# OBD.net
KiCad netlist of a schematic drawn in Altium Designer
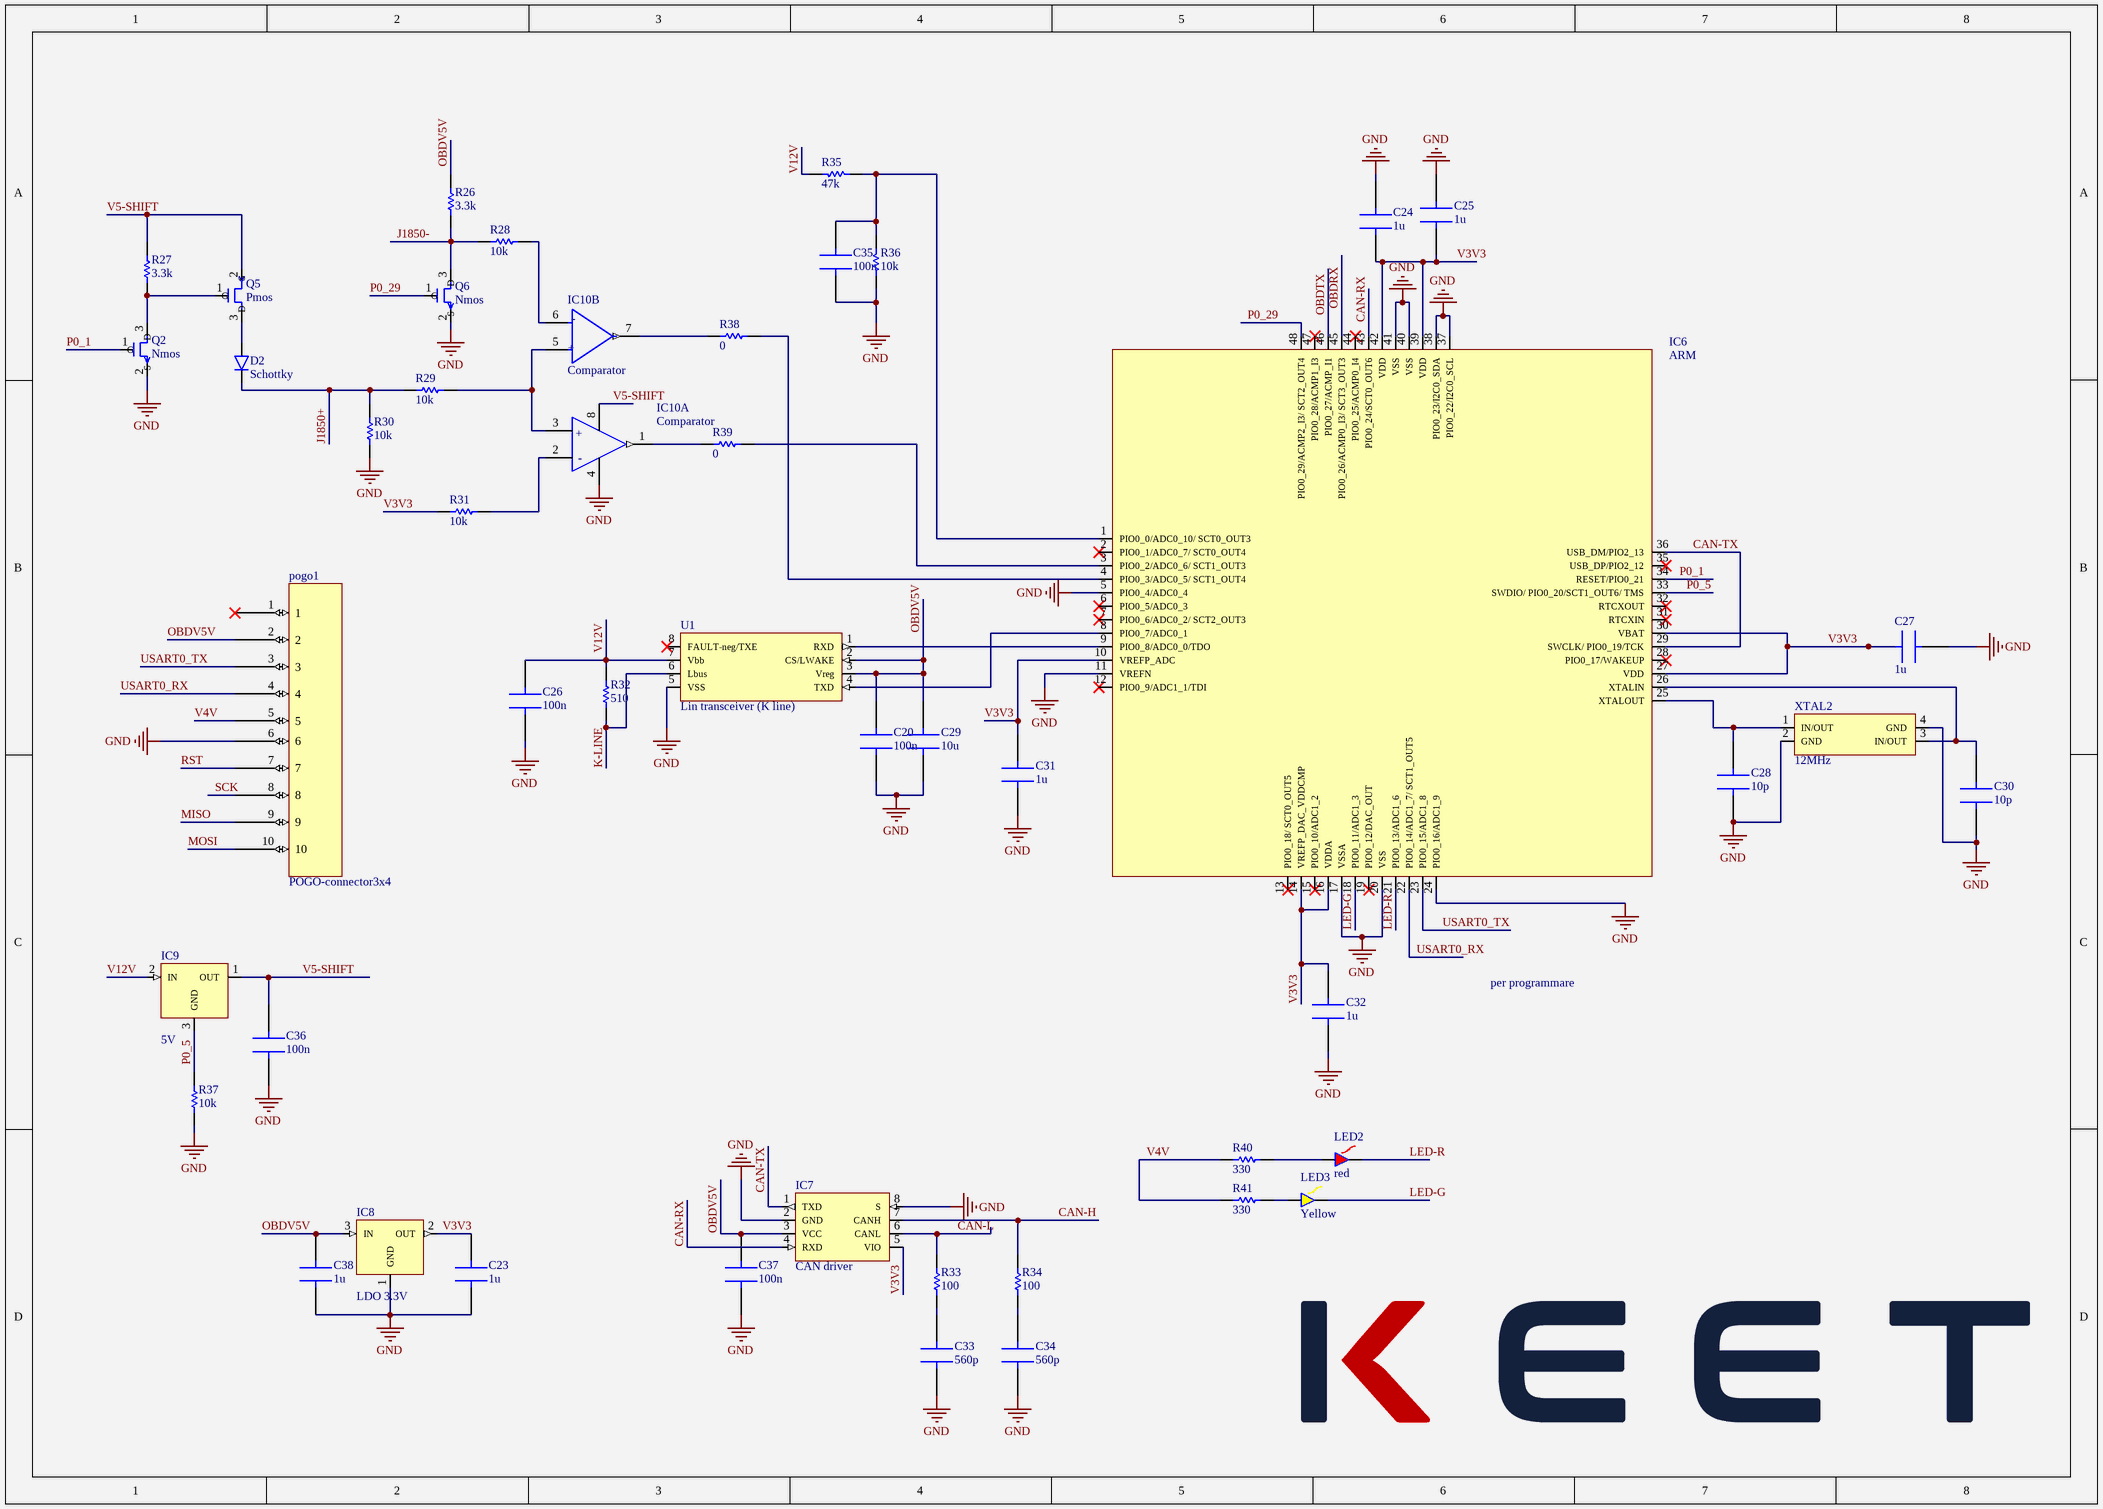
[diagram p0: OBD.SchDoc]

(export (version "E")
  (design (tool "Eeschema 10.0.6"))
  (components
    (comp (ref "C20")
      (value "100n")
      (footprint "CAPC1005X06N")
      (description "CAP CER 0.1UF 50V X5R 0402")
      (fields
        (field (name "MANUFACTURER") "TDK")
        (field (name "MANUFACTURER PART NUMBER") "C1005X5R1H104K050BB")
      )
      (libsource (lib "KeetV2") (part "C1005X5R1H104K050BB"))
    )
    (comp (ref "C23")
      (value "1u")
      (footprint "CAPC1005X06N")
      (description "TAIYO YUDEN - EMK105BJ105KVHF - CAPACITOR,CERAMIC,0402,16V,X5R,1 F, 10% ROHS COMPLIANT: YES")
      (fields
        (field (name "MANUFACTURER") "Taiyo Yuden")
        (field (name "MANUFACTURER PART NUMBER") "EMK105BJ105KVHF")
      )
      (libsource (lib "KeetV2") (part "EMK105BJ105KVHF"))
    )
    (comp (ref "C24")
      (value "1u")
      (footprint "CAPC1005X06N")
      (description "TAIYO YUDEN - EMK105BJ105KVHF - CAPACITOR,CERAMIC,0402,16V,X5R,1 F, 10% ROHS COMPLIANT: YES")
      (fields
        (field (name "MANUFACTURER") "Taiyo Yuden")
        (field (name "MANUFACTURER PART NUMBER") "EMK105BJ105KVHF")
      )
      (libsource (lib "KeetV2") (part "EMK105BJ105KVHF"))
    )
    (comp (ref "C25")
      (value "1u")
      (footprint "CAPC1005X06N")
      (description "TAIYO YUDEN - EMK105BJ105KVHF - CAPACITOR,CERAMIC,0402,16V,X5R,1 F, 10% ROHS COMPLIANT: YES")
      (fields
        (field (name "MANUFACTURER") "Taiyo Yuden")
        (field (name "MANUFACTURER PART NUMBER") "EMK105BJ105KVHF")
      )
      (libsource (lib "KeetV2") (part "EMK105BJ105KVHF"))
    )
    (comp (ref "C26")
      (value "100n")
      (footprint "CAPC1005X06N")
      (description "CAP CER 0.1UF 50V X5R 0402")
      (fields
        (field (name "MANUFACTURER") "TDK")
        (field (name "MANUFACTURER PART NUMBER") "C1005X5R1H104K050BB")
      )
      (libsource (lib "KeetV2") (part "C1005X5R1H104K050BB"))
    )
    (comp (ref "C27")
      (value "1u")
      (footprint "CAPC1005X06N")
      (description "TAIYO YUDEN - EMK105BJ105KVHF - CAPACITOR,CERAMIC,0402,16V,X5R,1 F, 10% ROHS COMPLIANT: YES")
      (fields
        (field (name "MANUFACTURER") "Taiyo Yuden")
        (field (name "MANUFACTURER PART NUMBER") "EMK105BJ105KVHF")
      )
      (libsource (lib "KeetV2") (part "EMK105BJ105KVHF"))
    )
    (comp (ref "C28")
      (value "10p")
      (footprint "CAPC1005X06N")
      (fields
        (field (name "MANUFACTURER") "Kyocera AVX")
        (field (name "MANUFACTURER PART NUMBER") "04025A100JAT2A")
        (field (name "TOLERANCE") "5%")
      )
      (libsource (lib "KeetV2") (part "04025A100JAT2A"))
    )
    (comp (ref "C29")
      (value "10u")
      (footprint "CAPC1005X06N")
      (description "Multi-Layer Ceramic Capacitor 10uF X5R 20% 0402 Paper T/R")
      (fields
        (field (name "MANUFACTURER") "Murata")
        (field (name "MANUFACTURER PART NUMBER") "GRM155R60J106ME05J")
      )
      (libsource (lib "KeetV2") (part "GRM155R60J106ME05J"))
    )
    (comp (ref "C30")
      (value "10p")
      (footprint "CAPC1005X06N")
      (fields
        (field (name "MANUFACTURER") "Kyocera AVX")
        (field (name "MANUFACTURER PART NUMBER") "04025A100JAT2A")
        (field (name "TOLERANCE") "5%")
      )
      (libsource (lib "KeetV2") (part "04025A100JAT2A"))
    )
    (comp (ref "C31")
      (value "1u")
      (footprint "CAPC1005X06N")
      (description "TAIYO YUDEN - EMK105BJ105KVHF - CAPACITOR,CERAMIC,0402,16V,X5R,1 F, 10% ROHS COMPLIANT: YES")
      (fields
        (field (name "MANUFACTURER") "Taiyo Yuden")
        (field (name "MANUFACTURER PART NUMBER") "EMK105BJ105KVHF")
      )
      (libsource (lib "KeetV2") (part "EMK105BJ105KVHF"))
    )
    (comp (ref "C32")
      (value "1u")
      (footprint "CAPC1005X06N")
      (description "TAIYO YUDEN - EMK105BJ105KVHF - CAPACITOR,CERAMIC,0402,16V,X5R,1 F, 10% ROHS COMPLIANT: YES")
      (fields
        (field (name "MANUFACTURER") "Taiyo Yuden")
        (field (name "MANUFACTURER PART NUMBER") "EMK105BJ105KVHF")
      )
      (libsource (lib "KeetV2") (part "EMK105BJ105KVHF"))
    )
    (comp (ref "C33")
      (value "560p")
      (footprint "CAPC1005X06N")
      (description "CAP CER 560PF 50V X7R 0402")
      (fields
        (field (name "MANUFACTURER") "Yageo")
        (field (name "MANUFACTURER PART NUMBER") "CC0402KRX7R9BB561")
      )
      (libsource (lib "KeetV2") (part "CC0402KRX7R9BB561"))
    )
    (comp (ref "C34")
      (value "560p")
      (footprint "CAPC1005X06N")
      (description "CAP CER 560PF 50V X7R 0402")
      (fields
        (field (name "MANUFACTURER") "Yageo")
        (field (name "MANUFACTURER PART NUMBER") "CC0402KRX7R9BB561")
      )
      (libsource (lib "KeetV2") (part "CC0402KRX7R9BB561"))
    )
    (comp (ref "C35")
      (value "100n")
      (footprint "CAPC1005X06N")
      (description "CAP CER 0.1UF 16V X7R 0402")
      (fields
        (field (name "MANUFACTURER") "Murata")
        (field (name "MANUFACTURER PART NUMBER") "GRM155R71C104KA88D")
      )
      (libsource (lib "KeetV2") (part "GRM155R71C104KA88D"))
    )
    (comp (ref "C36")
      (value "100n")
      (footprint "CAPC1005X06N")
      (description "CAP CER 0.1UF 16V X7R 0402")
      (fields
        (field (name "MANUFACTURER") "Murata")
        (field (name "MANUFACTURER PART NUMBER") "GRM155R71C104KA88D")
      )
      (libsource (lib "KeetV2") (part "GRM155R71C104KA88D"))
    )
    (comp (ref "C37")
      (value "100n")
      (footprint "CAPC1005X06N")
      (description "CAP CER 0.1UF 50V X5R 0402")
      (fields
        (field (name "MANUFACTURER") "TDK")
        (field (name "MANUFACTURER PART NUMBER") "C1005X5R1H104K050BB")
      )
      (libsource (lib "KeetV2") (part "C1005X5R1H104K050BB"))
    )
    (comp (ref "C38")
      (value "1u")
      (footprint "CAPC1005X06N")
      (description "TAIYO YUDEN - EMK105BJ105KVHF - CAPACITOR,CERAMIC,0402,16V,X5R,1 F, 10% ROHS COMPLIANT: YES")
      (fields
        (field (name "MANUFACTURER") "Taiyo Yuden")
        (field (name "MANUFACTURER PART NUMBER") "EMK105BJ105KVHF")
      )
      (libsource (lib "KeetV2") (part "EMK105BJ105KVHF"))
    )
    (comp (ref "D2")
      (value "Schottky")
      (footprint "TSSOP0P370X135-2N")
      (description "Diode Schottky 100V 0.15A 2Pin SOD123")
      (fields (field (name "MANUFACTURER") "Diodes") (field (name "MANUFACTURER PART NUMBER") "BAT46W-7-F"))
      (libsource (lib "KeetV2") (part "BAT46W-7-F"))
    )
    (comp (ref "IC6")
      (value "ARM")
      (footprint "TSQFP50P898X898X160-48N")
      (description "IC MCU 32BIT 64KB FLASH 48LQFP")
      (fields
        (field (name "MANUFACTURER") "NXP Semiconductors")
        (field (name "MANUFACTURER PART NUMBER") "LPC1517JBD48E")
      )
      (libsource (lib "KeetV2") (part "LPC1517JBD48E"))
    )
    (comp (ref "IC7")
      (value "CAN driver")
      (footprint "SOP127P600X175-8N")
      (description "IC CAN TRANSEIVER HS 8SOIC")
      (fields
        (field (name "MANUFACTURER") "NXP Semiconductors")
        (field (name "MANUFACTURER PART NUMBER") "TJF1051T/3,118")
      )
      (libsource (lib "KeetV2") (part "TJF1051T/3,118"))
    )
    (comp (ref "IC8")
      (value "LDO 3.3V")
      (footprint "SOT95P240X135-3N")
      (description "IC REG LIN 3.3V 150MA SOT23R-3")
      (fields
        (field (name "MANUFACTURER") "Diodes")
        (field (name "MANUFACTURER PART NUMBER") "AP7313-33SRG-7")
      )
      (libsource (lib "KeetV2") (part "AP7313-33SRG-7"))
    )
    (comp (ref "IC9")
      (value "5V")
      (footprint "SOT95P237X111-3N-ver2")
      (description "IC REG LINEAR 5V 100MA SOT23-3")
      (fields
        (field (name "MANUFACTURER") "Texas Instruments")
        (field (name "MANUFACTURER PART NUMBER") "TLV76050DBZT")
      )
      (libsource (lib "KeetV2") (part "TLV76050DBZT"))
    )
    (comp (ref "IC10")
      (value "Comparator")
      (footprint "SOIC127P600X175-8N")
      (description "TEXAS INSTRUMENTS - LM393D - COMPARATOR DUAL, SMD, SOIC8, 393")
      (fields
        (field (name "MANUFACTURER") "Texas Instruments")
        (field (name "MANUFACTURER PART NUMBER") "LM393D")
      )
      (libsource (lib "KeetV2") (part "LM393D"))
    )
    (comp (ref "LED2")
      (value "red")
      (footprint "CAC-0P80X160-2N_ver2")
      (description "AVAGO TECHNOLOGIES - HSMS-C190 - LED, RED, 10MCD, 626NM")
      (fields
        (field (name "MANUFACTURER") "Broadcom Avago")
        (field (name "MANUFACTURER PART NUMBER") "HSMS-C190")
      )
      (libsource (lib "KeetV2") (part "HSMS-C190"))
    )
    (comp (ref "LED3")
      (value "Yellow")
      (footprint "CAC-0P80X160-2N_ver2")
      (fields
        (field (name "MANUFACTURER") "Broadcom Avago")
        (field (name "MANUFACTURER PART NUMBER") "HSMY-C190")
      )
      (libsource (lib "KeetV2") (part "HSMY-C190"))
    )
    (comp (ref "pogo1")
      (value "POGO-connector3x4")
      (footprint "POGO_connector_3x4")
      (description "pad layout for external pogo connector")
      (libsource (lib "KeetV2") (part "POGO-connector3x4"))
    )
    (comp (ref "Q2")
      (value "Nmos")
      (footprint "SOT95P240X135-3N")
      (description "Trans MOSFET N-CH 50V 0.22A 3-Pin SOT-23 T/R")
      (fields
        (field (name "MANUFACTURER") "ON Semiconductor / Fairchild")
        (field (name "MANUFACTURER PART NUMBER") "BSS138")
      )
      (libsource (lib "KeetV2") (part "BSS138"))
    )
    (comp (ref "Q5")
      (value "Pmos")
      (footprint "SOT95P237X111-3N")
      (description "On a Reel of 3000, P-Channel MOSFET, 130 mA, 50 V, 3-Pin SOT-23 ON Semiconductor BSS84LT1G")
      (fields
        (field (name "MANUFACTURER") "ON Semiconductor")
        (field (name "MANUFACTURER PART NUMBER") "BSS84LT1G")
      )
      (libsource (lib "KeetV2") (part "BSS84LT1G"))
    )
    (comp (ref "Q6")
      (value "Nmos")
      (footprint "SOT95P240X135-3N")
      (description "Trans MOSFET N-CH 50V 0.22A 3-Pin SOT-23 T/R")
      (fields
        (field (name "MANUFACTURER") "ON Semiconductor / Fairchild")
        (field (name "MANUFACTURER PART NUMBER") "BSS138")
      )
      (libsource (lib "KeetV2") (part "BSS138"))
    )
    (comp (ref "R26")
      (value "3.3k")
      (footprint "RESC1005X04N")
      (description "PANASONIC - ERJ2RKF3301X - RES, 3K3, 1%, 0.1W, 0402, THICK FILM")
      (fields
        (field (name "MANUFACTURER") "Panasonic")
        (field (name "MANUFACTURER PART NUMBER") "ERJ-2RKF3301X")
      )
      (libsource (lib "KeetV2") (part "ERJ-2RKF3301X"))
    )
    (comp (ref "R27")
      (value "3.3k")
      (footprint "RESC1005X04N")
      (description "PANASONIC - ERJ2RKF3301X - RES, 3K3, 1%, 0.1W, 0402, THICK FILM")
      (fields
        (field (name "MANUFACTURER") "Panasonic")
        (field (name "MANUFACTURER PART NUMBER") "ERJ-2RKF3301X")
      )
      (libsource (lib "KeetV2") (part "ERJ-2RKF3301X"))
    )
    (comp (ref "R28")
      (value "10k")
      (footprint "RESC1005X04N")
      (fields
        (field (name "MANUFACTURER") "Panasonic")
        (field (name "MANUFACTURER PART NUMBER") "ERJ-U02F1002X")
        (field (name "TOLERANCE") "1%")
      )
      (libsource (lib "KeetV2") (part "ERJ-U02F1002X"))
    )
    (comp (ref "R29")
      (value "10k")
      (footprint "RESC1005X04N")
      (fields
        (field (name "MANUFACTURER") "Panasonic")
        (field (name "MANUFACTURER PART NUMBER") "ERJ-U02F1002X")
        (field (name "TOLERANCE") "1%")
      )
      (libsource (lib "KeetV2") (part "ERJ-U02F1002X"))
    )
    (comp (ref "R30")
      (value "10k")
      (footprint "RESC1005X04N")
      (fields
        (field (name "MANUFACTURER") "Panasonic")
        (field (name "MANUFACTURER PART NUMBER") "ERJ-U02F1002X")
        (field (name "TOLERANCE") "1%")
      )
      (libsource (lib "KeetV2") (part "ERJ-U02F1002X"))
    )
    (comp (ref "R31")
      (value "10k")
      (footprint "RESC1005X04N")
      (fields
        (field (name "MANUFACTURER") "Panasonic")
        (field (name "MANUFACTURER PART NUMBER") "ERJ-U02F1002X")
        (field (name "TOLERANCE") "1%")
      )
      (libsource (lib "KeetV2") (part "ERJ-U02F1002X"))
    )
    (comp (ref "R32")
      (value "510")
      (footprint "RESC1005X04N")
      (description "Res Thick Film 0402 510 Ohm 1% 0.063W(1/16W) ±100ppm/C Pad SMD T/R")
      (fields
        (field (name "MANUFACTURER") "Vishay")
        (field (name "MANUFACTURER PART NUMBER") "CRCW0402510RFKEDC")
      )
      (libsource (lib "KeetV2") (part "CRCW0402510RFKEDC"))
    )
    (comp (ref "R33")
      (value "100")
      (footprint "RESC1005X04N")
      (description "RES SMD 100 OHM 0.5% 1/16W 0402")
      (fields
        (field (name "MANUFACTURER") "Panasonic")
        (field (name "MANUFACTURER PART NUMBER") "ERJ-2RHD1000X")
      )
      (libsource (lib "KeetV2") (part "ERJ-2RHD1000X"))
    )
    (comp (ref "R34")
      (value "100")
      (footprint "RESC1005X04N")
      (description "RES SMD 100 OHM 0.5% 1/16W 0402")
      (fields
        (field (name "MANUFACTURER") "Panasonic")
        (field (name "MANUFACTURER PART NUMBER") "ERJ-2RHD1000X")
      )
      (libsource (lib "KeetV2") (part "ERJ-2RHD1000X"))
    )
    (comp (ref "R35")
      (value "47k")
      (footprint "RESC1005X04N")
      (description "Resistor;  Thick Film;  47 Kilohms;  0.063 W;  1%;  SMT;  0402;  TCR 37 ppm/DegC")
      (fields
        (field (name "MANUFACTURER") "Vishay")
        (field (name "MANUFACTURER PART NUMBER") "CRCW040247K0FKED")
      )
      (libsource (lib "KeetV2") (part "CRCW040247K0FKED"))
    )
    (comp (ref "R36")
      (value "10k")
      (footprint "RESC1005X04N")
      (fields
        (field (name "MANUFACTURER") "Panasonic")
        (field (name "MANUFACTURER PART NUMBER") "ERJ-U02F1002X")
        (field (name "TOLERANCE") "1%")
      )
      (libsource (lib "KeetV2") (part "ERJ-U02F1002X"))
    )
    (comp (ref "R37")
      (value "10k")
      (footprint "RESC1005X04N")
      (description "Res Thick Film 0402 10K Ohm 1% 1/16W ±100ppm/°C Molded SMD Paper T/R")
      (fields
        (field (name "MANUFACTURER") "Vishay")
        (field (name "MANUFACTURER PART NUMBER") "CRCW0402-10K0FKED")
      )
      (libsource (lib "KeetV2") (part "CRCW0402-10K0FKED"))
    )
    (comp (ref "R38")
      (value "0")
      (footprint "RESC2012X06N")
      (description "Res Thick Film 0805 0 Ohm Epoxy Pad SMD T/R")
      (fields
        (field (name "MANUFACTURER") "Yageo")
        (field (name "MANUFACTURER PART NUMBER") "RC0805FR-070RL")
      )
      (libsource (lib "KeetV2") (part "RC0805FR-070RL"))
    )
    (comp (ref "R39")
      (value "0")
      (footprint "RESC2012X06N")
      (description "Res Thick Film 0805 0 Ohm Epoxy Pad SMD T/R")
      (fields
        (field (name "MANUFACTURER") "Yageo")
        (field (name "MANUFACTURER PART NUMBER") "RC0805FR-070RL")
      )
      (libsource (lib "KeetV2") (part "RC0805FR-070RL"))
    )
    (comp (ref "R40")
      (value "330")
      (footprint "RESC1005X04N")
      (description "Res Thick Film 0402 330 Ohm 1% 0.063W(1/16W) ±100ppm/C Pad SMD T/R")
      (fields
        (field (name "MANUFACTURER") "Yageo")
        (field (name "MANUFACTURER PART NUMBER") "RC0402FR-07330RL")
      )
      (libsource (lib "KeetV2") (part "RC0402FR-07330RL"))
    )
    (comp (ref "R41")
      (value "330")
      (footprint "RESC1005X04N")
      (description "Res Thick Film 0402 330 Ohm 1% 0.063W(1/16W) ±100ppm/C Pad SMD T/R")
      (fields
        (field (name "MANUFACTURER") "Yageo")
        (field (name "MANUFACTURER PART NUMBER") "RC0402FR-07330RL")
      )
      (libsource (lib "KeetV2") (part "RC0402FR-07330RL"))
    )
    (comp (ref "U1")
      (value "Lin transceiver (K line)")
      (footprint "SOP127P600X175-8N")
      (description "LIN Transceiver with Integrated Vreg 5V 20kBd Automotive 8-Pin SOIC N")
      (fields
        (field (name "MANUFACTURER") "Microchip")
        (field (name "MANUFACTURER PART NUMBER") "MCP2021-500E/SN")
      )
      (libsource (lib "KeetV2") (part "MCP2021-500E/SN"))
    )
    (comp (ref "XTAL2")
      (value "12MHz")
      (footprint "DFN170P250X60-4N")
      (description "Crystal 12MHz ±10ppm (Tol) ±15ppm (Stability) 10pF FUND 130Ohm 4-Pin Mini-CSMD T/R")
      (fields
        (field (name "MANUFACTURER") "ECS International")
        (field (name "MANUFACTURER PART NUMBER") "ECS-120-10-36B-CWY-TR")
      )
      (libsource (lib "KeetV2") (part "ECS-120-10-36B-CWY-TR"))
    )
  )
  (nets
    (net (code "1") (name "/CAN-H") (class "Default")
      (node (ref "IC7") (pin "7") (pinfunction "CANH_7") (pintype "bidirectional"))
      (node (ref "R34") (pin "2") (pinfunction "2_2") (pintype "passive"))
    )
    (net (code "2") (name "/CAN-L") (class "Default")
      (node (ref "IC7") (pin "6") (pinfunction "CANL_6") (pintype "bidirectional"))
      (node (ref "R33") (pin "2") (pinfunction "2_2") (pintype "passive"))
    )
    (net (code "3") (name "/CAN-RX") (class "Default")
      (node (ref "IC6") (pin "43") (pinfunction "PIO0_24/SCT0_OUT6_43") (pintype "passive"))
      (node (ref "IC7") (pin "4") (pinfunction "RXD_4") (pintype "input"))
    )
    (net (code "4") (name "/CAN-TX") (class "Default")
      (node (ref "IC6") (pin "29") (pinfunction "SWCLK/_PIO0_19/TCK_29") (pintype "passive"))
      (node (ref "IC6") (pin "36") (pinfunction "USB_DM/PIO2_13_36") (pintype "passive"))
      (node (ref "IC7") (pin "1") (pinfunction "TXD_1") (pintype "output"))
    )
    (net (code "5") (name "/J1850+") (class "Default")
      (node (ref "D2") (pin "2") (pinfunction "K_2") (pintype "passive"))
      (node (ref "R29") (pin "1") (pinfunction "1_1") (pintype "passive"))
      (node (ref "R30") (pin "2") (pinfunction "2_2") (pintype "passive"))
    )
    (net (code "6") (name "/J1850-") (class "Default")
      (node (ref "Q6") (pin "3") (pinfunction "D_3") (pintype "passive"))
      (node (ref "R26") (pin "1") (pinfunction "1_1") (pintype "passive"))
      (node (ref "R28") (pin "1") (pinfunction "1_1") (pintype "passive"))
    )
    (net (code "7") (name "/K-LINE") (class "Default")
      (node (ref "R32") (pin "1") (pinfunction "1_1") (pintype "passive"))
      (node (ref "U1") (pin "6") (pinfunction "Lbus_6") (pintype "bidirectional"))
    )
    (net (code "8") (name "/LED-G") (class "Default")
      (node (ref "IC6") (pin "18") (pinfunction "PIO0_11/ADC1_3_18") (pintype "passive"))
      (node (ref "LED3") (pin "1") (pinfunction "K_1") (pintype "passive"))
    )
    (net (code "9") (name "/LED-R") (class "Default")
      (node (ref "IC6") (pin "21") (pinfunction "PIO0_13/ADC1_6_21") (pintype "passive"))
      (node (ref "LED2") (pin "1") (pinfunction "K_1") (pintype "passive"))
    )
    (net (code "10") (name "/MISO") (class "Default")
      (node (ref "pogo1") (pin "9") (pinfunction "9_9") (pintype "bidirectional"))
    )
    (net (code "11") (name "/MOSI") (class "Default")
      (node (ref "pogo1") (pin "10") (pinfunction "10_10") (pintype "bidirectional"))
    )
    (net (code "12") (name "/OBDRX") (class "Default")
      (node (ref "IC6") (pin "45") (pinfunction "PIO0_26/ACMP0_I3/_SCT3_OUT3_45") (pintype "passive"))
    )
    (net (code "13") (name "/OBDTX") (class "Default")
      (node (ref "IC6") (pin "46") (pinfunction "PIO0_27/ACMP_I1_46") (pintype "passive"))
    )
    (net (code "14") (name "/OBDV5V") (class "Default")
      (node (ref "C20") (pin "2") (pinfunction "2_2") (pintype "passive"))
      (node (ref "C29") (pin "2") (pinfunction "2_2") (pintype "passive"))
      (node (ref "C37") (pin "2") (pinfunction "2_2") (pintype "passive"))
      (node (ref "C38") (pin "1") (pinfunction "1_1") (pintype "passive"))
      (node (ref "IC7") (pin "3") (pinfunction "VCC_3") (pintype "passive"))
      (node (ref "IC8") (pin "3") (pinfunction "IN_3") (pintype "input"))
      (node (ref "R26") (pin "2") (pinfunction "2_2") (pintype "passive"))
      (node (ref "U1") (pin "2") (pinfunction "CS/LWAKE_2") (pintype "input"))
      (node (ref "U1") (pin "3") (pinfunction "Vreg_3") (pintype "passive"))
      (node (ref "pogo1") (pin "2") (pinfunction "2_2") (pintype "bidirectional"))
    )
    (net (code "15") (name "/P0_1") (class "Default")
      (node (ref "IC6") (pin "34") (pinfunction "RESET/PIO0_21_34") (pintype "passive"))
      (node (ref "Q2") (pin "1") (pinfunction "G_1") (pintype "passive"))
    )
    (net (code "16") (name "/P0_5") (class "Default")
      (node (ref "IC6") (pin "33") (pinfunction "SWDIO/_PIO0_20/SCT1_OUT6/_TMS_33") (pintype "passive"))
      (node (ref "IC9") (pin "3") (pinfunction "GND_3") (pintype "passive"))
      (node (ref "R37") (pin "2") (pinfunction "2_2") (pintype "passive"))
    )
    (net (code "17") (name "/P0_29") (class "Default")
      (node (ref "IC6") (pin "48") (pinfunction "PIO0_29/ACMP2_I3/_SCT2_OUT4_48") (pintype "passive"))
      (node (ref "Q6") (pin "1") (pinfunction "G_1") (pintype "passive"))
    )
    (net (code "18") (name "/RST") (class "Default")
      (node (ref "pogo1") (pin "7") (pinfunction "7_7") (pintype "bidirectional"))
    )
    (net (code "19") (name "/SCK") (class "Default")
      (node (ref "pogo1") (pin "8") (pinfunction "8_8") (pintype "bidirectional"))
    )
    (net (code "20") (name "/USART0_RX") (class "Default")
      (node (ref "IC6") (pin "22") (pinfunction "PIO0_14/ADC1_7/_SCT1_OUT5_22") (pintype "passive"))
      (node (ref "pogo1") (pin "4") (pinfunction "4_4") (pintype "bidirectional"))
    )
    (net (code "21") (name "/USART0_TX") (class "Default")
      (node (ref "IC6") (pin "23") (pinfunction "PIO0_15/ADC1_8_23") (pintype "passive"))
      (node (ref "pogo1") (pin "3") (pinfunction "3_3") (pintype "bidirectional"))
    )
    (net (code "22") (name "/V3V3") (class "Default")
      (node (ref "C23") (pin "1") (pinfunction "1_1") (pintype "passive"))
      (node (ref "C24") (pin "1") (pinfunction "1_1") (pintype "passive"))
      (node (ref "C25") (pin "1") (pinfunction "1_1") (pintype "passive"))
      (node (ref "C27") (pin "1") (pinfunction "1_1") (pintype "passive"))
      (node (ref "C31") (pin "1") (pinfunction "1_1") (pintype "passive"))
      (node (ref "C32") (pin "2") (pinfunction "2_2") (pintype "passive"))
      (node (ref "IC6") (pin "10") (pinfunction "VREFP_ADC_10") (pintype "passive"))
      (node (ref "IC6") (pin "14") (pinfunction "VREFP_DAC_VDDCMP_14") (pintype "passive"))
      (node (ref "IC6") (pin "16") (pinfunction "VDDA_16") (pintype "passive"))
      (node (ref "IC6") (pin "27") (pinfunction "VDD_27") (pintype "passive"))
      (node (ref "IC6") (pin "30") (pinfunction "VBAT_30") (pintype "passive"))
      (node (ref "IC6") (pin "39") (pinfunction "VDD_39") (pintype "passive"))
      (node (ref "IC6") (pin "42") (pinfunction "VDD_42") (pintype "passive"))
      (node (ref "IC7") (pin "5") (pinfunction "VIO_5") (pintype "passive"))
      (node (ref "IC8") (pin "2") (pinfunction "OUT_2") (pintype "output"))
      (node (ref "R31") (pin "1") (pinfunction "1_1") (pintype "passive"))
    )
    (net (code "23") (name "/V4V") (class "Default")
      (node (ref "R40") (pin "1") (pinfunction "1_1") (pintype "passive"))
      (node (ref "R41") (pin "1") (pinfunction "1_1") (pintype "passive"))
      (node (ref "pogo1") (pin "5") (pinfunction "5_5") (pintype "bidirectional"))
    )
    (net (code "24") (name "/V5-SHIFT") (class "Default")
      (node (ref "C36") (pin "2") (pinfunction "2_2") (pintype "passive"))
      (node (ref "IC10") (pin "8") (pinfunction "Vcc+_8") (pintype "power_in"))
      (node (ref "IC9") (pin "1") (pinfunction "OUT_1") (pintype "passive"))
      (node (ref "Q5") (pin "2") (pinfunction "S_2") (pintype "passive"))
      (node (ref "R27") (pin "2") (pinfunction "2_2") (pintype "passive"))
    )
    (net (code "25") (name "/V12V") (class "Default")
      (node (ref "C26") (pin "2") (pinfunction "2_2") (pintype "passive"))
      (node (ref "IC9") (pin "2") (pinfunction "IN_2") (pintype "input"))
      (node (ref "R32") (pin "2") (pinfunction "2_2") (pintype "passive"))
      (node (ref "R35") (pin "2") (pinfunction "2_2") (pintype "passive"))
      (node (ref "U1") (pin "7") (pinfunction "Vbb_7") (pintype "passive"))
    )
    (net (code "26") (name "GND") (class "Default")
      (node (ref "C20") (pin "1") (pinfunction "1_1") (pintype "passive"))
      (node (ref "C23") (pin "2") (pinfunction "2_2") (pintype "passive"))
      (node (ref "C24") (pin "2") (pinfunction "2_2") (pintype "passive"))
      (node (ref "C25") (pin "2") (pinfunction "2_2") (pintype "passive"))
      (node (ref "C26") (pin "1") (pinfunction "1_1") (pintype "passive"))
      (node (ref "C27") (pin "2") (pinfunction "2_2") (pintype "passive"))
      (node (ref "C28") (pin "1") (pinfunction "1_1") (pintype "passive"))
      (node (ref "C29") (pin "1") (pinfunction "1_1") (pintype "passive"))
      (node (ref "C30") (pin "1") (pinfunction "1_1") (pintype "passive"))
      (node (ref "C31") (pin "2") (pinfunction "2_2") (pintype "passive"))
      (node (ref "C32") (pin "1") (pinfunction "1_1") (pintype "passive"))
      (node (ref "C33") (pin "2") (pinfunction "2_2") (pintype "passive"))
      (node (ref "C34") (pin "2") (pinfunction "2_2") (pintype "passive"))
      (node (ref "C35") (pin "1") (pinfunction "1_1") (pintype "passive"))
      (node (ref "C36") (pin "1") (pinfunction "1_1") (pintype "passive"))
      (node (ref "C37") (pin "1") (pinfunction "1_1") (pintype "passive"))
      (node (ref "C38") (pin "2") (pinfunction "2_2") (pintype "passive"))
      (node (ref "IC10") (pin "4") (pinfunction "Vcc-_4") (pintype "power_in"))
      (node (ref "IC6") (pin "11") (pinfunction "VREFN_11") (pintype "passive"))
      (node (ref "IC6") (pin "17") (pinfunction "VSSA_17") (pintype "passive"))
      (node (ref "IC6") (pin "20") (pinfunction "VSS_20") (pintype "passive"))
      (node (ref "IC6") (pin "24") (pinfunction "PIO0_16/ADC1_9_24") (pintype "passive"))
      (node (ref "IC6") (pin "37") (pinfunction "PIO0_22/I2C0_SCL_37") (pintype "passive"))
      (node (ref "IC6") (pin "38") (pinfunction "PIO0_23/I2C0_SDA_38") (pintype "passive"))
      (node (ref "IC6") (pin "40") (pinfunction "VSS_40") (pintype "passive"))
      (node (ref "IC6") (pin "41") (pinfunction "VSS_41") (pintype "passive"))
      (node (ref "IC6") (pin "5") (pinfunction "PIO0_4/ADC0_4_5") (pintype "passive"))
      (node (ref "IC7") (pin "2") (pinfunction "GND_2") (pintype "passive"))
      (node (ref "IC7") (pin "8") (pinfunction "S_8") (pintype "input"))
      (node (ref "IC8") (pin "1") (pinfunction "GND_1") (pintype "passive"))
      (node (ref "Q2") (pin "2") (pinfunction "S_2") (pintype "passive"))
      (node (ref "Q6") (pin "2") (pinfunction "S_2") (pintype "passive"))
      (node (ref "R30") (pin "1") (pinfunction "1_1") (pintype "passive"))
      (node (ref "R36") (pin "1") (pinfunction "1_1") (pintype "passive"))
      (node (ref "R37") (pin "1") (pinfunction "1_1") (pintype "passive"))
      (node (ref "U1") (pin "5") (pinfunction "VSS_5") (pintype "passive"))
      (node (ref "XTAL2") (pin "2") (pinfunction "GND_2") (pintype "passive"))
      (node (ref "XTAL2") (pin "4") (pinfunction "GND_4") (pintype "passive"))
      (node (ref "pogo1") (pin "6") (pinfunction "6_6") (pintype "bidirectional"))
    )
    (net (code "27") (name "Net-(C33-Pad1)") (class "Default")
      (node (ref "C33") (pin "1") (pinfunction "1_1") (pintype "passive"))
      (node (ref "R33") (pin "1") (pinfunction "1_1") (pintype "passive"))
    )
    (net (code "28") (name "Net-(C34-Pad1)") (class "Default")
      (node (ref "C34") (pin "1") (pinfunction "1_1") (pintype "passive"))
      (node (ref "R34") (pin "1") (pinfunction "1_1") (pintype "passive"))
    )
    (net (code "29") (name "Net-(D2-A)") (class "Default")
      (node (ref "D2") (pin "1") (pinfunction "A_1") (pintype "passive"))
      (node (ref "Q5") (pin "3") (pinfunction "D_3") (pintype "passive"))
    )
    (net (code "30") (name "Net-(IC6-PIO0_0{slash}ADC0_10{slash}_SCT0_OUT3)") (class "Default")
      (node (ref "C35") (pin "2") (pinfunction "2_2") (pintype "passive"))
      (node (ref "IC6") (pin "1") (pinfunction "PIO0_0/ADC0_10/_SCT0_OUT3_1") (pintype "passive"))
      (node (ref "R35") (pin "1") (pinfunction "1_1") (pintype "passive"))
      (node (ref "R36") (pin "2") (pinfunction "2_2") (pintype "passive"))
    )
    (net (code "31") (name "Net-(IC6-PIO0_2{slash}ADC0_6{slash}_SCT1_OUT3)") (class "Default")
      (node (ref "IC6") (pin "3") (pinfunction "PIO0_2/ADC0_6/_SCT1_OUT3_3") (pintype "passive"))
      (node (ref "R39") (pin "2") (pinfunction "2_2") (pintype "passive"))
    )
    (net (code "32") (name "Net-(IC6-PIO0_3{slash}ADC0_5{slash}_SCT1_OUT4)") (class "Default")
      (node (ref "IC6") (pin "4") (pinfunction "PIO0_3/ADC0_5/_SCT1_OUT4_4") (pintype "passive"))
      (node (ref "R38") (pin "2") (pinfunction "2_2") (pintype "passive"))
    )
    (net (code "33") (name "Net-(IC6-PIO0_7{slash}ADC0_1)") (class "Default")
      (node (ref "IC6") (pin "8") (pinfunction "PIO0_7/ADC0_1_8") (pintype "passive"))
      (node (ref "U1") (pin "4") (pinfunction "TXD_4") (pintype "input"))
    )
    (net (code "34") (name "Net-(IC6-PIO0_8{slash}ADC0_0{slash}TDO)") (class "Default")
      (node (ref "IC6") (pin "9") (pinfunction "PIO0_8/ADC0_0/TDO_9") (pintype "passive"))
      (node (ref "U1") (pin "1") (pinfunction "RXD_1") (pintype "output"))
    )
    (net (code "35") (name "Net-(IC6-XTALIN)") (class "Default")
      (node (ref "C30") (pin "2") (pinfunction "2_2") (pintype "passive"))
      (node (ref "IC6") (pin "26") (pinfunction "XTALIN_26") (pintype "passive"))
      (node (ref "XTAL2") (pin "3") (pinfunction "IN/OUT_3") (pintype "passive"))
    )
    (net (code "36") (name "Net-(IC6-XTALOUT)") (class "Default")
      (node (ref "C28") (pin "2") (pinfunction "2_2") (pintype "passive"))
      (node (ref "IC6") (pin "25") (pinfunction "XTALOUT_25") (pintype "passive"))
      (node (ref "XTAL2") (pin "1") (pinfunction "IN/OUT_1") (pintype "passive"))
    )
    (net (code "37") (name "Net-(IC10A-In1+)") (class "Default")
      (node (ref "IC10") (pin "3") (pinfunction "In1+_3") (pintype "tri_state"))
      (node (ref "IC10") (pin "5") (pinfunction "In2+_5") (pintype "tri_state"))
      (node (ref "R29") (pin "2") (pinfunction "2_2") (pintype "passive"))
    )
    (net (code "38") (name "Net-(IC10A-In1-)") (class "Default")
      (node (ref "IC10") (pin "2") (pinfunction "In1-_2") (pintype "tri_state"))
      (node (ref "R31") (pin "2") (pinfunction "2_2") (pintype "passive"))
    )
    (net (code "39") (name "Net-(IC10A-Out1)") (class "Default")
      (node (ref "IC10") (pin "1") (pinfunction "Out1_1") (pintype "output"))
      (node (ref "R39") (pin "1") (pinfunction "1_1") (pintype "passive"))
    )
    (net (code "40") (name "Net-(IC10B-In2-)") (class "Default")
      (node (ref "IC10") (pin "6") (pinfunction "In2-_6") (pintype "tri_state"))
      (node (ref "R28") (pin "2") (pinfunction "2_2") (pintype "passive"))
    )
    (net (code "41") (name "Net-(IC10B-Out2)") (class "Default")
      (node (ref "IC10") (pin "7") (pinfunction "Out2_7") (pintype "output"))
      (node (ref "R38") (pin "1") (pinfunction "1_1") (pintype "passive"))
    )
    (net (code "42") (name "Net-(LED2-A)") (class "Default")
      (node (ref "LED2") (pin "2") (pinfunction "A_2") (pintype "passive"))
      (node (ref "R40") (pin "2") (pinfunction "2_2") (pintype "passive"))
    )
    (net (code "43") (name "Net-(LED3-A)") (class "Default")
      (node (ref "LED3") (pin "2") (pinfunction "A_2") (pintype "passive"))
      (node (ref "R41") (pin "2") (pinfunction "2_2") (pintype "passive"))
    )
    (net (code "44") (name "Net-(Q2-D)") (class "Default")
      (node (ref "Q2") (pin "3") (pinfunction "D_3") (pintype "passive"))
      (node (ref "Q5") (pin "1") (pinfunction "G_1") (pintype "passive"))
      (node (ref "R27") (pin "1") (pinfunction "1_1") (pintype "passive"))
    )
    (net (code "45") (name "unconnected-(IC6-PIO0_1{slash}ADC0_7{slash}_SCT0_OUT4-Pad2)") (class "Default")
      (node (ref "IC6") (pin "2") (pinfunction "PIO0_1/ADC0_7/_SCT0_OUT4_2") (pintype "passive+no_connect"))
    )
    (net (code "46") (name "unconnected-(IC6-PIO0_5{slash}ADC0_3-Pad6)") (class "Default")
      (node (ref "IC6") (pin "6") (pinfunction "PIO0_5/ADC0_3_6") (pintype "passive+no_connect"))
    )
    (net (code "47") (name "unconnected-(IC6-PIO0_6{slash}ADC0_2{slash}_SCT2_OUT3-Pad7)") (class "Default")
      (node (ref "IC6") (pin "7") (pinfunction "PIO0_6/ADC0_2/_SCT2_OUT3_7") (pintype "passive+no_connect"))
    )
    (net (code "48") (name "unconnected-(IC6-PIO0_9{slash}ADC1_1{slash}TDI-Pad12)") (class "Default")
      (node (ref "IC6") (pin "12") (pinfunction "PIO0_9/ADC1_1/TDI_12") (pintype "passive+no_connect"))
    )
    (net (code "49") (name "unconnected-(IC6-PIO0_10{slash}ADC1_2-Pad15)") (class "Default")
      (node (ref "IC6") (pin "15") (pinfunction "PIO0_10/ADC1_2_15") (pintype "passive+no_connect"))
    )
    (net (code "50") (name "unconnected-(IC6-PIO0_12{slash}DAC_OUT-Pad19)") (class "Default")
      (node (ref "IC6") (pin "19") (pinfunction "PIO0_12/DAC_OUT_19") (pintype "passive+no_connect"))
    )
    (net (code "51") (name "unconnected-(IC6-PIO0_17{slash}WAKEUP-Pad28)") (class "Default")
      (node (ref "IC6") (pin "28") (pinfunction "PIO0_17/WAKEUP_28") (pintype "passive+no_connect"))
    )
    (net (code "52") (name "unconnected-(IC6-PIO0_18{slash}_SCT0_OUT5-Pad13)") (class "Default")
      (node (ref "IC6") (pin "13") (pinfunction "PIO0_18/_SCT0_OUT5_13") (pintype "passive+no_connect"))
    )
    (net (code "53") (name "unconnected-(IC6-PIO0_25{slash}ACMP0_I4-Pad44)") (class "Default")
      (node (ref "IC6") (pin "44") (pinfunction "PIO0_25/ACMP0_I4_44") (pintype "passive+no_connect"))
    )
    (net (code "54") (name "unconnected-(IC6-PIO0_28{slash}ACMP1_I3-Pad47)") (class "Default")
      (node (ref "IC6") (pin "47") (pinfunction "PIO0_28/ACMP1_I3_47") (pintype "passive+no_connect"))
    )
    (net (code "55") (name "unconnected-(IC6-RTCXIN-Pad31)") (class "Default")
      (node (ref "IC6") (pin "31") (pinfunction "RTCXIN_31") (pintype "passive+no_connect"))
    )
    (net (code "56") (name "unconnected-(IC6-RTCXOUT-Pad32)") (class "Default")
      (node (ref "IC6") (pin "32") (pinfunction "RTCXOUT_32") (pintype "passive+no_connect"))
    )
    (net (code "57") (name "unconnected-(IC6-USB_DP{slash}PIO2_12-Pad35)") (class "Default")
      (node (ref "IC6") (pin "35") (pinfunction "USB_DP/PIO2_12_35") (pintype "passive+no_connect"))
    )
    (net (code "58") (name "unconnected-(U1-FAULT-neg{slash}TXE-Pad8)") (class "Default")
      (node (ref "U1") (pin "8") (pinfunction "FAULT-neg/TXE_8") (pintype "bidirectional+no_connect"))
    )
    (net (code "59") (name "unconnected-(pogo1-Pad1)") (class "Default")
      (node (ref "pogo1") (pin "1") (pinfunction "1_1") (pintype "bidirectional+no_connect"))
    )
  )
)
